# Camera.net
KiCad netlist of a schematic drawn in Altium Designer
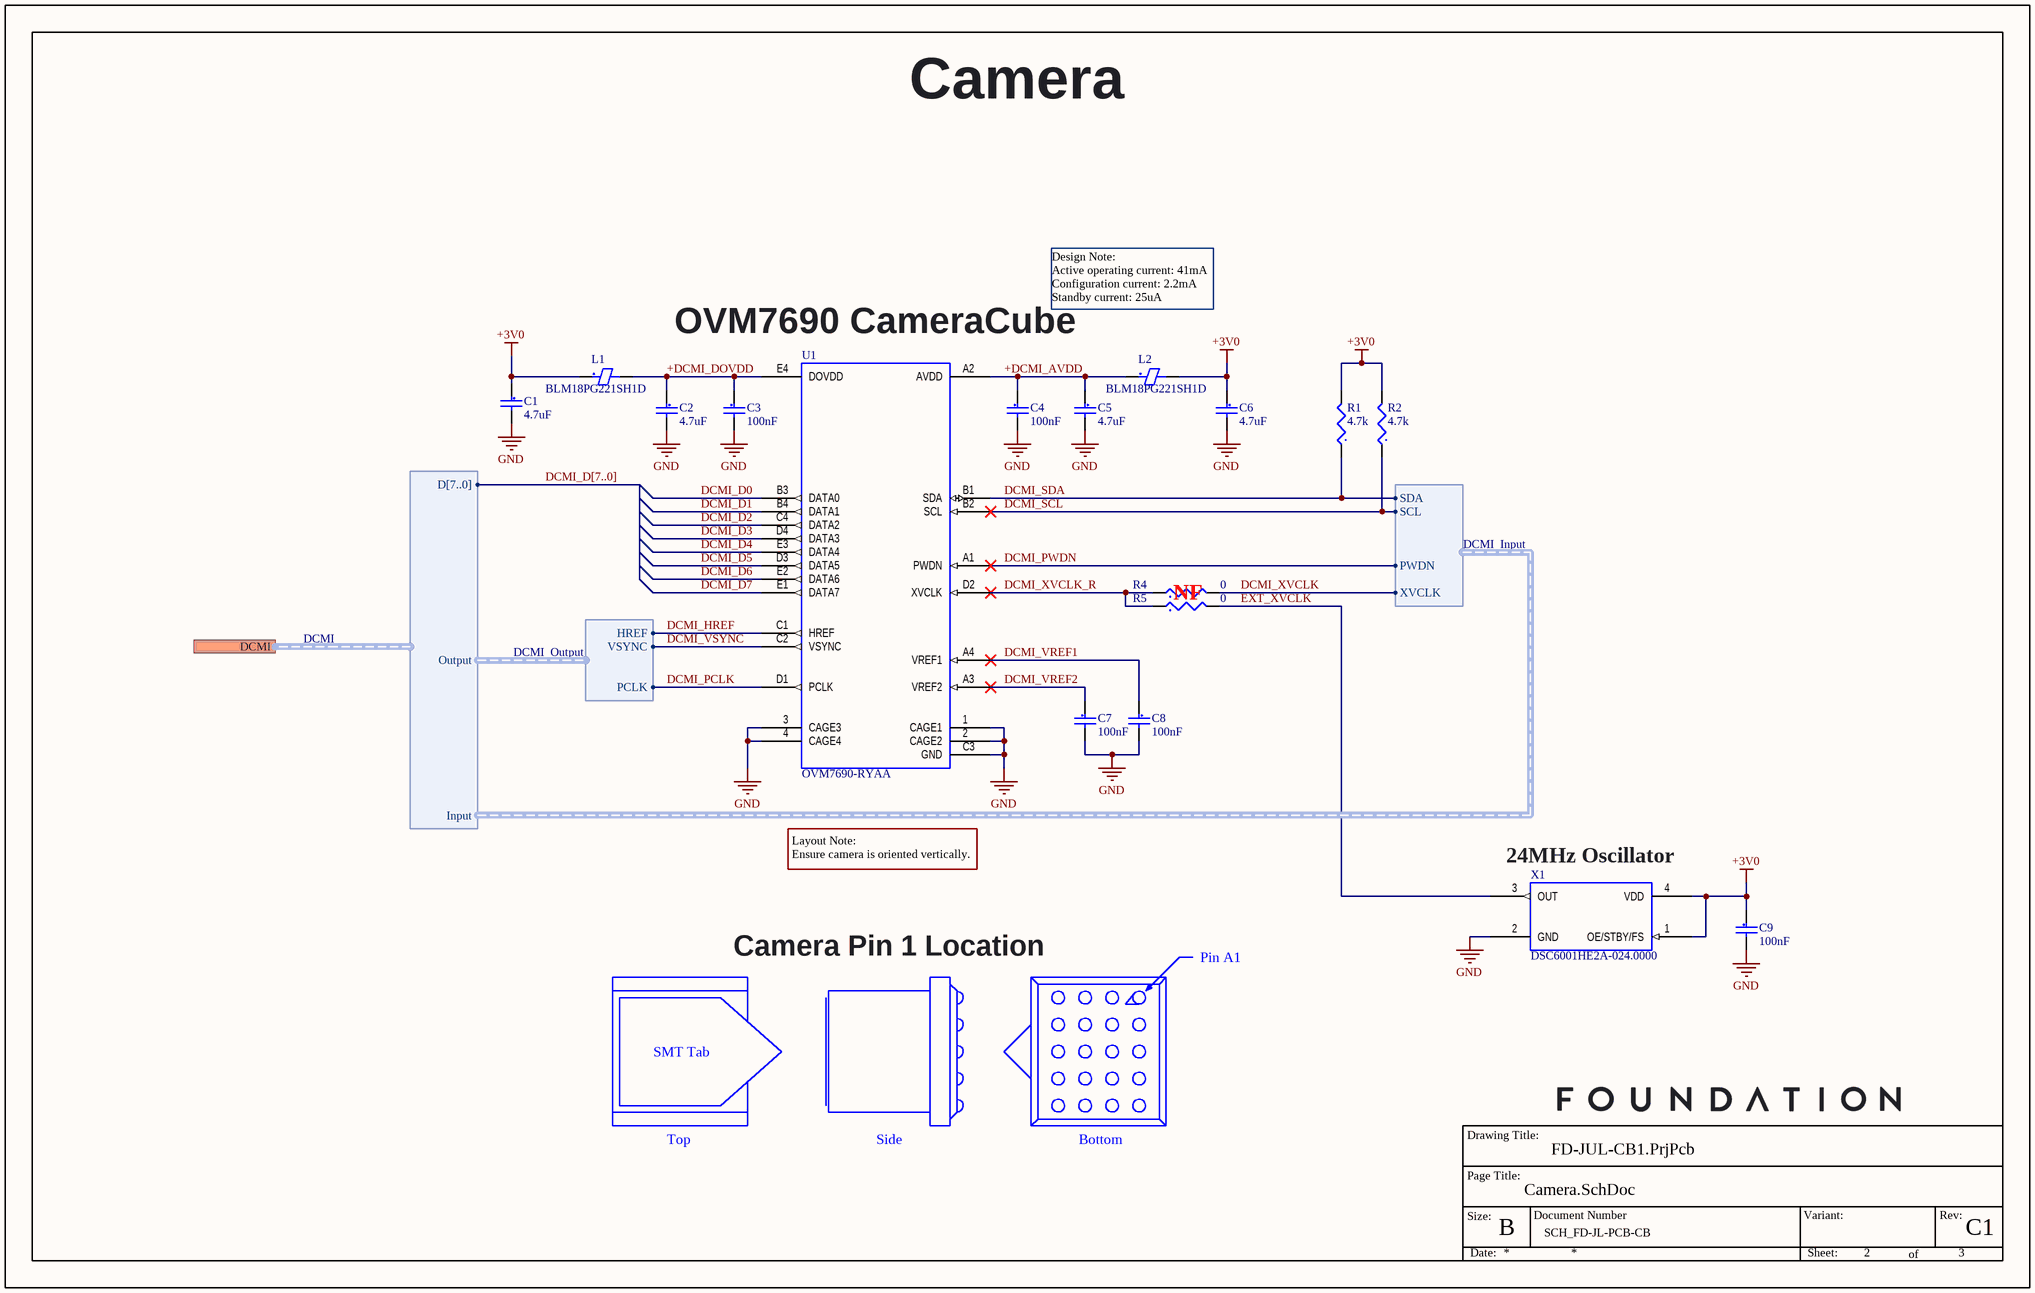
[diagram p0: Camera.SchDoc]

(export (version "E")
  (design (tool "Eeschema 10.0.6"))
  (components
    (comp (ref "C1")
      (value "CAP CER 4.7uF 16V 10% X5R 0603")
      (footprint "CAPC0603(1608)90_L")
      (description "4.7µF ±10% 16V Ceramic Capacitor X5R 0603 (1608 Metric)")
      (fields (field (name "CAPACITANCE") "4.7uF") (field (name "TOLERANCE") "10%"))
      (libsource (lib "Altium Concord Pro on A365") (part "CAP-NP-2"))
    )
    (comp (ref "C2")
      (value "CAP CER 4.7uF 16V 10% X5R 0603")
      (footprint "CAPC0603(1608)90_L")
      (description "4.7µF ±10% 16V Ceramic Capacitor X5R 0603 (1608 Metric)")
      (fields (field (name "CAPACITANCE") "4.7uF") (field (name "TOLERANCE") "10%"))
      (libsource (lib "Altium Concord Pro on A365") (part "CAP-NP-2"))
    )
    (comp (ref "C3")
      (value "CAP CER 0.1uF 16V 10% X7R 0402")
      (footprint "CAPC0402(1005)55_L")
      (description "0.1µF ±10% 16V Ceramic Capacitor X7R 0402 (1005 Metric)")
      (fields
        (field (name "CAPACITANCE") "100nF")
        (field (name "TOLERANCE") "10%")
        (field (name "VOLTAGE") "16V")
      )
      (libsource (lib "Altium Concord Pro on A365") (part "CAP-NP-2"))
    )
    (comp (ref "C4")
      (value "CAP CER 0.1uF 16V 10% X7R 0402")
      (footprint "CAPC0402(1005)55_L")
      (description "0.1µF ±10% 16V Ceramic Capacitor X7R 0402 (1005 Metric)")
      (fields
        (field (name "CAPACITANCE") "100nF")
        (field (name "TOLERANCE") "10%")
        (field (name "VOLTAGE") "16V")
      )
      (libsource (lib "Altium Concord Pro on A365") (part "CAP-NP-2"))
    )
    (comp (ref "C5")
      (value "CAP CER 4.7uF 16V 10% X5R 0603")
      (footprint "CAPC0603(1608)90_L")
      (description "4.7µF ±10% 16V Ceramic Capacitor X5R 0603 (1608 Metric)")
      (fields (field (name "CAPACITANCE") "4.7uF") (field (name "TOLERANCE") "10%"))
      (libsource (lib "Altium Concord Pro on A365") (part "CAP-NP-2"))
    )
    (comp (ref "C6")
      (value "CAP CER 4.7uF 16V 10% X5R 0603")
      (footprint "CAPC0603(1608)90_L")
      (description "4.7µF ±10% 16V Ceramic Capacitor X5R 0603 (1608 Metric)")
      (fields (field (name "CAPACITANCE") "4.7uF") (field (name "TOLERANCE") "10%"))
      (libsource (lib "Altium Concord Pro on A365") (part "CAP-NP-2"))
    )
    (comp (ref "C7")
      (value "CAP CER 0.1uF 16V 10% X7R 0402")
      (footprint "CAPC0402(1005)55_L")
      (description "0.1µF ±10% 16V Ceramic Capacitor X7R 0402 (1005 Metric)")
      (fields
        (field (name "CAPACITANCE") "100nF")
        (field (name "TOLERANCE") "10%")
        (field (name "VOLTAGE") "16V")
      )
      (libsource (lib "Altium Concord Pro on A365") (part "CAP-NP-2"))
    )
    (comp (ref "C8")
      (value "CAP CER 0.1uF 16V 10% X7R 0402")
      (footprint "CAPC0402(1005)55_L")
      (description "0.1µF ±10% 16V Ceramic Capacitor X7R 0402 (1005 Metric)")
      (fields
        (field (name "CAPACITANCE") "100nF")
        (field (name "TOLERANCE") "10%")
        (field (name "VOLTAGE") "16V")
      )
      (libsource (lib "Altium Concord Pro on A365") (part "CAP-NP-2"))
    )
    (comp (ref "C9")
      (value "CAP CER 0.1uF 16V 10% X7R 0402")
      (footprint "CAPC0402(1005)55_L")
      (description "0.1µF ±10% 16V Ceramic Capacitor X7R 0402 (1005 Metric)")
      (fields
        (field (name "CAPACITANCE") "100nF")
        (field (name "TOLERANCE") "10%")
        (field (name "VOLTAGE") "16V")
      )
      (libsource (lib "Altium Concord Pro on A365") (part "CAP-NP-2"))
    )
    (comp (ref "L1")
      (value "BLM18PG221SH1D")
      (footprint "FBC0603(1608)90_L")
      (description "FERRITE BEAD 220 OHM 0603 1LN")
      (fields (field (name "TOLERANCE") "25%"))
      (libsource (lib "Altium Concord Pro on A365") (part "FB-NP-2"))
    )
    (comp (ref "L2")
      (value "BLM18PG221SH1D")
      (footprint "FBC0603(1608)90_L")
      (description "FERRITE BEAD 220 OHM 0603 1LN")
      (fields (field (name "TOLERANCE") "25%"))
      (libsource (lib "Altium Concord Pro on A365") (part "FB-NP-2"))
    )
    (comp (ref "R1")
      (value "RES 4.7K 1/16W 1% 0402")
      (footprint "RESC0402(1005)_L")
      (description "4.7 kOhms ±1% 0.063W, 1/16W Chip Resistor 0402 (1005 Metric) Automotive AEC-Q200 Thick Film")
      (fields (field (name "RESISTANCE") "4.7k") (field (name "TOLERANCE") "1%"))
      (libsource (lib "Altium Concord Pro on A365") (part "RES-2"))
    )
    (comp (ref "R2")
      (value "RES 4.7K 1/16W 1% 0402")
      (footprint "RESC0402(1005)_L")
      (description "4.7 kOhms ±1% 0.063W, 1/16W Chip Resistor 0402 (1005 Metric) Automotive AEC-Q200 Thick Film")
      (fields (field (name "RESISTANCE") "4.7k") (field (name "TOLERANCE") "1%"))
      (libsource (lib "Altium Concord Pro on A365") (part "RES-2"))
    )
    (comp (ref "R4")
      (value "RES 0 OHM JUMPER 1/16W 0402")
      (footprint "RESC0402(1005)_L")
      (description "0 Ohms Jumper 0.063W, 1/16W Chip Resistor 0402 (1005 Metric)")
      (fields (field (name "RESISTANCE") "0") (field (name "TOLERANCE") "5%"))
      (libsource (lib "Altium Concord Pro on A365") (part "RES-2"))
    )
    (comp (ref "R5")
      (value "RES 0 OHM JUMPER 1/16W 0402")
      (footprint "RESC0402(1005)_L")
      (description "0 Ohms Jumper 0.063W, 1/16W Chip Resistor 0402 (1005 Metric)")
      (fields (field (name "RESISTANCE") "0") (field (name "TOLERANCE") "5%"))
      (libsource (lib "Altium Concord Pro on A365") (part "RES-2"))
    )
    (comp (ref "U1")
      (value "OVM7690-RYAA")
      (footprint "OMNI - CCBGA-CG-20")
      (description "SENSOR CAMERA CMOS 20CAMERACUBE")
      (libsource (lib "Altium Concord Pro on A365") (part "OVM7690-RYAA"))
    )
    (comp (ref "X1")
      (value "DSC6001HE2A-024.0000")
      (footprint "MCHP - VFLGA-1612-4_L")
      (description "XO (Standard) CMOS Oscillator 1.8V ~ 3.3V Enable/Disable 4-SMD, No Lead")
      (libsource (lib "Altium Concord Pro on A365") (part "DSC60XX"))
    )
  )
  (nets
    (net (code "4") (name "+3V0") (class "Default")
      (node (ref "C1") (pin "1") (pinfunction "1_1") (pintype "passive"))
      (node (ref "C6") (pin "1") (pinfunction "1_1") (pintype "passive"))
      (node (ref "C9") (pin "1") (pinfunction "1_1") (pintype "passive"))
      (node (ref "L1") (pin "1") (pinfunction "1_1") (pintype "passive"))
      (node (ref "L2") (pin "2") (pinfunction "2_2") (pintype "passive"))
      (node (ref "R1") (pin "2") (pinfunction "2_2") (pintype "passive"))
      (node (ref "R2") (pin "2") (pinfunction "2_2") (pintype "passive"))
      (node (ref "X1") (pin "1") (pinfunction "OE/STBY/FS_1") (pintype "input"))
      (node (ref "X1") (pin "4") (pinfunction "VDD_4") (pintype "power_in"))
    )
    (net (code "5") (name "/+DCMI_AVDD") (class "Default")
      (node (ref "C4") (pin "1") (pinfunction "1_1") (pintype "passive"))
      (node (ref "C5") (pin "1") (pinfunction "1_1") (pintype "passive"))
      (node (ref "L2") (pin "1") (pinfunction "1_1") (pintype "passive"))
      (node (ref "U1") (pin "A2") (pinfunction "AVDD_A2") (pintype "power_in"))
    )
    (net (code "6") (name "/+DCMI_DOVDD") (class "Default")
      (node (ref "C2") (pin "1") (pinfunction "1_1") (pintype "passive"))
      (node (ref "C3") (pin "1") (pinfunction "1_1") (pintype "passive"))
      (node (ref "L1") (pin "2") (pinfunction "2_2") (pintype "passive"))
      (node (ref "U1") (pin "E4") (pinfunction "DOVDD_E4") (pintype "power_in"))
    )
    (net (code "7") (name "/DCMI_D0") (class "Default")
      (node (ref "U1") (pin "B3") (pinfunction "DATA0_B3") (pintype "output"))
    )
    (net (code "8") (name "/DCMI_D1") (class "Default")
      (node (ref "U1") (pin "B4") (pinfunction "DATA1_B4") (pintype "output"))
    )
    (net (code "9") (name "/DCMI_D2") (class "Default")
      (node (ref "U1") (pin "C4") (pinfunction "DATA2_C4") (pintype "output"))
    )
    (net (code "10") (name "/DCMI_D3") (class "Default")
      (node (ref "U1") (pin "D4") (pinfunction "DATA3_D4") (pintype "output"))
    )
    (net (code "11") (name "/DCMI_D4") (class "Default")
      (node (ref "U1") (pin "E3") (pinfunction "DATA4_E3") (pintype "output"))
    )
    (net (code "12") (name "/DCMI_D5") (class "Default")
      (node (ref "U1") (pin "D3") (pinfunction "DATA5_D3") (pintype "output"))
    )
    (net (code "13") (name "/DCMI_D6") (class "Default")
      (node (ref "U1") (pin "E2") (pinfunction "DATA6_E2") (pintype "output"))
    )
    (net (code "14") (name "/DCMI_D7") (class "Default")
      (node (ref "U1") (pin "E1") (pinfunction "DATA7_E1") (pintype "output"))
    )
    (net (code "15") (name "/DCMI_HREF") (class "Default")
      (node (ref "U1") (pin "C1") (pinfunction "HREF_C1") (pintype "output"))
    )
    (net (code "16") (name "/DCMI_PCLK") (class "Default")
      (node (ref "U1") (pin "D1") (pinfunction "PCLK_D1") (pintype "output"))
    )
    (net (code "17") (name "/DCMI_PWDN") (class "Default")
      (node (ref "U1") (pin "A1") (pinfunction "PWDN_A1") (pintype "input+no_connect"))
    )
    (net (code "18") (name "/DCMI_SCL") (class "Default")
      (node (ref "R2") (pin "1") (pinfunction "1_1") (pintype "passive"))
      (node (ref "U1") (pin "B2") (pinfunction "SCL_B2") (pintype "input"))
    )
    (net (code "19") (name "/DCMI_SDA") (class "Default")
      (node (ref "R1") (pin "1") (pinfunction "1_1") (pintype "passive"))
      (node (ref "U1") (pin "B1") (pinfunction "SDA_B1") (pintype "bidirectional"))
    )
    (net (code "20") (name "/DCMI_VREF1") (class "Default")
      (node (ref "C8") (pin "1") (pinfunction "1_1") (pintype "passive"))
      (node (ref "U1") (pin "A4") (pinfunction "VREF1_A4") (pintype "input"))
    )
    (net (code "21") (name "/DCMI_VREF2") (class "Default")
      (node (ref "C7") (pin "1") (pinfunction "1_1") (pintype "passive"))
      (node (ref "U1") (pin "A3") (pinfunction "VREF2_A3") (pintype "input"))
    )
    (net (code "22") (name "/DCMI_VSYNC") (class "Default")
      (node (ref "U1") (pin "C2") (pinfunction "VSYNC_C2") (pintype "output"))
    )
    (net (code "23") (name "/DCMI_XVCLK") (class "Default")
      (node (ref "R4") (pin "2") (pinfunction "2_2") (pintype "passive"))
    )
    (net (code "24") (name "/DCMI_XVCLK_R") (class "Default")
      (node (ref "R4") (pin "1") (pinfunction "1_1") (pintype "passive"))
      (node (ref "R5") (pin "1") (pinfunction "1_1") (pintype "passive"))
      (node (ref "U1") (pin "D2") (pinfunction "XVCLK_D2") (pintype "input"))
    )
    (net (code "26") (name "/EXT_XVCLK") (class "Default")
      (node (ref "R5") (pin "2") (pinfunction "2_2") (pintype "passive"))
      (node (ref "X1") (pin "3") (pinfunction "OUT_3") (pintype "output"))
    )
    (net (code "30") (name "GND") (class "Default")
      (node (ref "C1") (pin "2") (pinfunction "2_2") (pintype "passive"))
      (node (ref "C2") (pin "2") (pinfunction "2_2") (pintype "passive"))
      (node (ref "C3") (pin "2") (pinfunction "2_2") (pintype "passive"))
      (node (ref "C4") (pin "2") (pinfunction "2_2") (pintype "passive"))
      (node (ref "C5") (pin "2") (pinfunction "2_2") (pintype "passive"))
      (node (ref "C6") (pin "2") (pinfunction "2_2") (pintype "passive"))
      (node (ref "C7") (pin "2") (pinfunction "2_2") (pintype "passive"))
      (node (ref "C8") (pin "2") (pinfunction "2_2") (pintype "passive"))
      (node (ref "C9") (pin "2") (pinfunction "2_2") (pintype "passive"))
      (node (ref "U1") (pin "1") (pinfunction "CAGE1_1") (pintype "power_in"))
      (node (ref "U1") (pin "2") (pinfunction "CAGE2_2") (pintype "power_in"))
      (node (ref "U1") (pin "3") (pinfunction "CAGE3_3") (pintype "power_in"))
      (node (ref "U1") (pin "4") (pinfunction "CAGE4_4") (pintype "power_in"))
      (node (ref "U1") (pin "C3") (pinfunction "GND_C3") (pintype "power_in"))
      (node (ref "X1") (pin "2") (pinfunction "GND_2") (pintype "passive"))
    )
  )
)
